# S02-BEAGLEBONE.net
KiCad netlist of a schematic drawn in Altium Designer
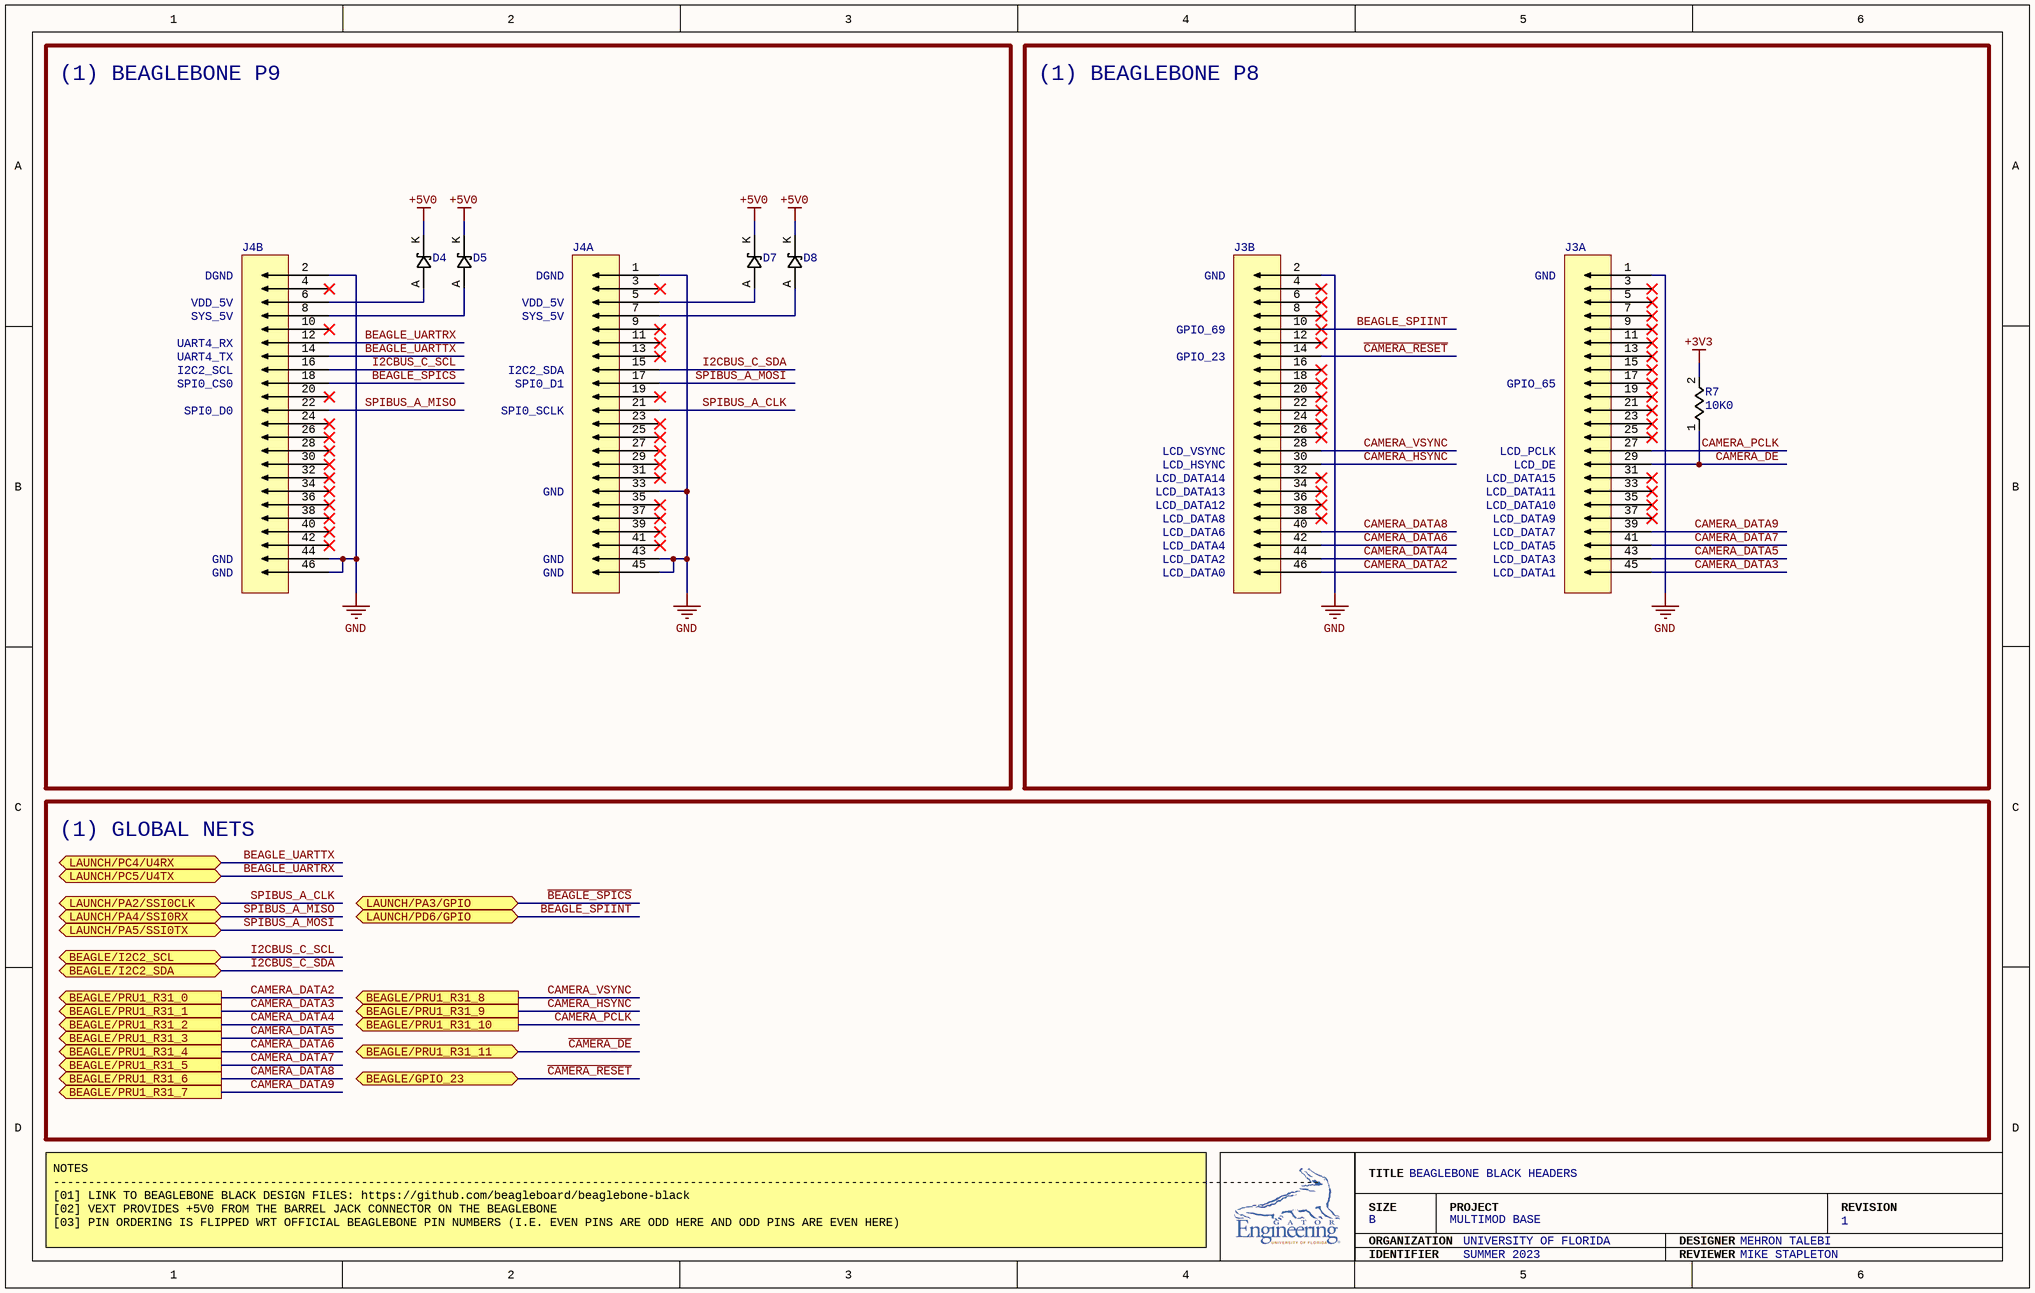
[diagram p0: S02-BEAGLEBONE.SchDoc]

(export (version "E")
  (design (tool "Eeschema 10.0.6"))
  (components
    (comp (ref "D4")
      (value "RBR5L30BDDTE25")
      (footprint "RBR5L30BDDTE25")
      (description "DIODE SCHOTTKY 30V 5A PMDS")
      (libsource (lib "Master") (part "RBR5L30BDDTE25"))
    )
    (comp (ref "D5")
      (value "RBR5L30BDDTE25")
      (footprint "RBR5L30BDDTE25")
      (description "DIODE SCHOTTKY 30V 5A PMDS")
      (libsource (lib "Master") (part "RBR5L30BDDTE25"))
    )
    (comp (ref "D7")
      (value "RBR5L30BDDTE25")
      (footprint "RBR5L30BDDTE25")
      (description "DIODE SCHOTTKY 30V 5A PMDS")
      (libsource (lib "Master") (part "RBR5L30BDDTE25"))
    )
    (comp (ref "D8")
      (value "RBR5L30BDDTE25")
      (footprint "RBR5L30BDDTE25")
      (description "DIODE SCHOTTKY 30V 5A PMDS")
      (libsource (lib "Master") (part "RBR5L30BDDTE25"))
    )
    (comp (ref "J3")
      (value "95278-101-46LF")
      (footprint "95278-101-46LF")
      (description "CONN HEADER SMD 46POS 2.54MM")
      (libsource (lib "Master") (part "95278-101-46LF"))
    )
    (comp (ref "J4")
      (value "95278-101-46LF")
      (footprint "95278-101-46LF")
      (description "CONN HEADER SMD 46POS 2.54MM")
      (libsource (lib "Master") (part "95278-101-46LF"))
    )
    (comp (ref "R7")
      (value "10K0")
      (footprint "RC0805FR-0710KL")
      (description "RES 10K OHM 1% 1/8W 0805")
      (fields (field (name "TOLERANCE") "±1%"))
      (libsource (lib "Master") (part "RC0805FR-0710KL"))
    )
  )
  (nets
    (net (code "1") (name "+3V3") (class "Default")
      (node (ref "R7") (pin "2") (pinfunction "2_2") (pintype "passive"))
    )
    (net (code "2") (name "+5V0") (class "Default")
      (node (ref "D4") (pin "K") (pinfunction "+_K") (pintype "passive"))
      (node (ref "D5") (pin "K") (pinfunction "+_K") (pintype "passive"))
      (node (ref "D7") (pin "K") (pinfunction "+_K") (pintype "passive"))
      (node (ref "D8") (pin "K") (pinfunction "+_K") (pintype "passive"))
    )
    (net (code "3") (name "/BEAGLE_SPICS") (class "Default")
      (node (ref "J4") (pin "18") (pinfunction "18_18") (pintype "passive"))
    )
    (net (code "4") (name "/BEAGLE_SPIINT") (class "Default")
      (node (ref "J3") (pin "10") (pinfunction "10_10") (pintype "passive"))
    )
    (net (code "5") (name "/BEAGLE_UARTRX") (class "Default")
      (node (ref "J4") (pin "12") (pinfunction "12_12") (pintype "passive"))
    )
    (net (code "6") (name "/BEAGLE_UARTTX") (class "Default")
      (node (ref "J4") (pin "14") (pinfunction "14_14") (pintype "passive"))
    )
    (net (code "7") (name "/CAMERA_DATA2") (class "Default")
      (node (ref "J3") (pin "46") (pinfunction "46_46") (pintype "passive"))
    )
    (net (code "8") (name "/CAMERA_DATA3") (class "Default")
      (node (ref "J3") (pin "45") (pinfunction "45_45") (pintype "passive"))
    )
    (net (code "9") (name "/CAMERA_DATA4") (class "Default")
      (node (ref "J3") (pin "44") (pinfunction "44_44") (pintype "passive"))
    )
    (net (code "10") (name "/CAMERA_DATA5") (class "Default")
      (node (ref "J3") (pin "43") (pinfunction "43_43") (pintype "passive"))
    )
    (net (code "11") (name "/CAMERA_DATA6") (class "Default")
      (node (ref "J3") (pin "42") (pinfunction "42_42") (pintype "passive"))
    )
    (net (code "12") (name "/CAMERA_DATA7") (class "Default")
      (node (ref "J3") (pin "41") (pinfunction "41_41") (pintype "passive"))
    )
    (net (code "13") (name "/CAMERA_DATA8") (class "Default")
      (node (ref "J3") (pin "40") (pinfunction "40_40") (pintype "passive"))
    )
    (net (code "14") (name "/CAMERA_DATA9") (class "Default")
      (node (ref "J3") (pin "39") (pinfunction "39_39") (pintype "passive"))
    )
    (net (code "15") (name "/CAMERA_DE") (class "Default")
      (node (ref "J3") (pin "29") (pinfunction "29_29") (pintype "passive"))
      (node (ref "R7") (pin "1") (pinfunction "1_1") (pintype "passive"))
    )
    (net (code "16") (name "/CAMERA_HSYNC") (class "Default")
      (node (ref "J3") (pin "30") (pinfunction "30_30") (pintype "passive"))
    )
    (net (code "17") (name "/CAMERA_PCLK") (class "Default")
      (node (ref "J3") (pin "27") (pinfunction "27_27") (pintype "passive"))
    )
    (net (code "18") (name "/CAMERA_RESET") (class "Default")
      (node (ref "J3") (pin "14") (pinfunction "14_14") (pintype "passive"))
    )
    (net (code "19") (name "/CAMERA_VSYNC") (class "Default")
      (node (ref "J3") (pin "28") (pinfunction "28_28") (pintype "passive"))
    )
    (net (code "20") (name "/I2CBUS_C_SCL") (class "Default")
      (node (ref "J4") (pin "16") (pinfunction "16_16") (pintype "passive"))
    )
    (net (code "21") (name "/I2CBUS_C_SDA") (class "Default")
      (node (ref "J4") (pin "15") (pinfunction "15_15") (pintype "passive"))
    )
    (net (code "22") (name "/SPIBUS_A_CLK") (class "Default")
      (node (ref "J4") (pin "21") (pinfunction "21_21") (pintype "passive"))
    )
    (net (code "23") (name "/SPIBUS_A_MISO") (class "Default")
      (node (ref "J4") (pin "22") (pinfunction "22_22") (pintype "passive"))
    )
    (net (code "24") (name "/SPIBUS_A_MOSI") (class "Default")
      (node (ref "J4") (pin "17") (pinfunction "17_17") (pintype "passive"))
    )
    (net (code "25") (name "GND") (class "Default")
      (node (ref "J3") (pin "1") (pinfunction "1_1") (pintype "passive"))
      (node (ref "J3") (pin "2") (pinfunction "2_2") (pintype "passive"))
      (node (ref "J4") (pin "1") (pinfunction "1_1") (pintype "passive"))
      (node (ref "J4") (pin "2") (pinfunction "2_2") (pintype "passive"))
      (node (ref "J4") (pin "33") (pinfunction "33_33") (pintype "passive"))
      (node (ref "J4") (pin "43") (pinfunction "43_43") (pintype "passive"))
      (node (ref "J4") (pin "44") (pinfunction "44_44") (pintype "passive"))
      (node (ref "J4") (pin "45") (pinfunction "45_45") (pintype "passive"))
      (node (ref "J4") (pin "46") (pinfunction "46_46") (pintype "passive"))
    )
    (net (code "26") (name "Net-(D4--)") (class "Default")
      (node (ref "D4") (pin "A") (pinfunction "-_A") (pintype "passive"))
      (node (ref "J4") (pin "6") (pinfunction "6_6") (pintype "passive"))
    )
    (net (code "27") (name "Net-(D5--)") (class "Default")
      (node (ref "D5") (pin "A") (pinfunction "-_A") (pintype "passive"))
      (node (ref "J4") (pin "8") (pinfunction "8_8") (pintype "passive"))
    )
    (net (code "28") (name "Net-(D7--)") (class "Default")
      (node (ref "D7") (pin "A") (pinfunction "-_A") (pintype "passive"))
      (node (ref "J4") (pin "5") (pinfunction "5_5") (pintype "passive"))
    )
    (net (code "29") (name "Net-(D8--)") (class "Default")
      (node (ref "D8") (pin "A") (pinfunction "-_A") (pintype "passive"))
      (node (ref "J4") (pin "7") (pinfunction "7_7") (pintype "passive"))
    )
    (net (code "30") (name "unconnected-(J3-Pad3)") (class "Default")
      (node (ref "J3") (pin "3") (pinfunction "3_3") (pintype "passive+no_connect"))
    )
    (net (code "31") (name "unconnected-(J3-Pad4)") (class "Default")
      (node (ref "J3") (pin "4") (pinfunction "4_4") (pintype "passive+no_connect"))
    )
    (net (code "32") (name "unconnected-(J3-Pad5)") (class "Default")
      (node (ref "J3") (pin "5") (pinfunction "5_5") (pintype "passive+no_connect"))
    )
    (net (code "33") (name "unconnected-(J3-Pad6)") (class "Default")
      (node (ref "J3") (pin "6") (pinfunction "6_6") (pintype "passive+no_connect"))
    )
    (net (code "34") (name "unconnected-(J3-Pad7)") (class "Default")
      (node (ref "J3") (pin "7") (pinfunction "7_7") (pintype "passive+no_connect"))
    )
    (net (code "35") (name "unconnected-(J3-Pad8)") (class "Default")
      (node (ref "J3") (pin "8") (pinfunction "8_8") (pintype "passive+no_connect"))
    )
    (net (code "36") (name "unconnected-(J3-Pad9)") (class "Default")
      (node (ref "J3") (pin "9") (pinfunction "9_9") (pintype "passive+no_connect"))
    )
    (net (code "37") (name "unconnected-(J3-Pad11)") (class "Default")
      (node (ref "J3") (pin "11") (pinfunction "11_11") (pintype "passive+no_connect"))
    )
    (net (code "38") (name "unconnected-(J3-Pad12)") (class "Default")
      (node (ref "J3") (pin "12") (pinfunction "12_12") (pintype "passive+no_connect"))
    )
    (net (code "39") (name "unconnected-(J3-Pad13)") (class "Default")
      (node (ref "J3") (pin "13") (pinfunction "13_13") (pintype "passive+no_connect"))
    )
    (net (code "40") (name "unconnected-(J3-Pad15)") (class "Default")
      (node (ref "J3") (pin "15") (pinfunction "15_15") (pintype "passive+no_connect"))
    )
    (net (code "41") (name "unconnected-(J3-Pad16)") (class "Default")
      (node (ref "J3") (pin "16") (pinfunction "16_16") (pintype "passive+no_connect"))
    )
    (net (code "42") (name "unconnected-(J3-Pad17)") (class "Default")
      (node (ref "J3") (pin "17") (pinfunction "17_17") (pintype "passive+no_connect"))
    )
    (net (code "43") (name "unconnected-(J3-Pad18)") (class "Default")
      (node (ref "J3") (pin "18") (pinfunction "18_18") (pintype "passive+no_connect"))
    )
    (net (code "44") (name "unconnected-(J3-Pad19)") (class "Default")
      (node (ref "J3") (pin "19") (pinfunction "19_19") (pintype "passive+no_connect"))
    )
    (net (code "45") (name "unconnected-(J3-Pad20)") (class "Default")
      (node (ref "J3") (pin "20") (pinfunction "20_20") (pintype "passive+no_connect"))
    )
    (net (code "46") (name "unconnected-(J3-Pad21)") (class "Default")
      (node (ref "J3") (pin "21") (pinfunction "21_21") (pintype "passive+no_connect"))
    )
    (net (code "47") (name "unconnected-(J3-Pad22)") (class "Default")
      (node (ref "J3") (pin "22") (pinfunction "22_22") (pintype "passive+no_connect"))
    )
    (net (code "48") (name "unconnected-(J3-Pad23)") (class "Default")
      (node (ref "J3") (pin "23") (pinfunction "23_23") (pintype "passive+no_connect"))
    )
    (net (code "49") (name "unconnected-(J3-Pad24)") (class "Default")
      (node (ref "J3") (pin "24") (pinfunction "24_24") (pintype "passive+no_connect"))
    )
    (net (code "50") (name "unconnected-(J3-Pad25)") (class "Default")
      (node (ref "J3") (pin "25") (pinfunction "25_25") (pintype "passive+no_connect"))
    )
    (net (code "51") (name "unconnected-(J3-Pad26)") (class "Default")
      (node (ref "J3") (pin "26") (pinfunction "26_26") (pintype "passive+no_connect"))
    )
    (net (code "52") (name "unconnected-(J3-Pad31)") (class "Default")
      (node (ref "J3") (pin "31") (pinfunction "31_31") (pintype "passive+no_connect"))
    )
    (net (code "53") (name "unconnected-(J3-Pad32)") (class "Default")
      (node (ref "J3") (pin "32") (pinfunction "32_32") (pintype "passive+no_connect"))
    )
    (net (code "54") (name "unconnected-(J3-Pad33)") (class "Default")
      (node (ref "J3") (pin "33") (pinfunction "33_33") (pintype "passive+no_connect"))
    )
    (net (code "55") (name "unconnected-(J3-Pad34)") (class "Default")
      (node (ref "J3") (pin "34") (pinfunction "34_34") (pintype "passive+no_connect"))
    )
    (net (code "56") (name "unconnected-(J3-Pad35)") (class "Default")
      (node (ref "J3") (pin "35") (pinfunction "35_35") (pintype "passive+no_connect"))
    )
    (net (code "57") (name "unconnected-(J3-Pad36)") (class "Default")
      (node (ref "J3") (pin "36") (pinfunction "36_36") (pintype "passive+no_connect"))
    )
    (net (code "58") (name "unconnected-(J3-Pad37)") (class "Default")
      (node (ref "J3") (pin "37") (pinfunction "37_37") (pintype "passive+no_connect"))
    )
    (net (code "59") (name "unconnected-(J3-Pad38)") (class "Default")
      (node (ref "J3") (pin "38") (pinfunction "38_38") (pintype "passive+no_connect"))
    )
    (net (code "60") (name "unconnected-(J4-Pad3)") (class "Default")
      (node (ref "J4") (pin "3") (pinfunction "3_3") (pintype "passive+no_connect"))
    )
    (net (code "61") (name "unconnected-(J4-Pad4)") (class "Default")
      (node (ref "J4") (pin "4") (pinfunction "4_4") (pintype "passive+no_connect"))
    )
    (net (code "62") (name "unconnected-(J4-Pad9)") (class "Default")
      (node (ref "J4") (pin "9") (pinfunction "9_9") (pintype "passive+no_connect"))
    )
    (net (code "63") (name "unconnected-(J4-Pad10)") (class "Default")
      (node (ref "J4") (pin "10") (pinfunction "10_10") (pintype "passive+no_connect"))
    )
    (net (code "64") (name "unconnected-(J4-Pad11)") (class "Default")
      (node (ref "J4") (pin "11") (pinfunction "11_11") (pintype "passive+no_connect"))
    )
    (net (code "65") (name "unconnected-(J4-Pad13)") (class "Default")
      (node (ref "J4") (pin "13") (pinfunction "13_13") (pintype "passive+no_connect"))
    )
    (net (code "66") (name "unconnected-(J4-Pad19)") (class "Default")
      (node (ref "J4") (pin "19") (pinfunction "19_19") (pintype "passive+no_connect"))
    )
    (net (code "67") (name "unconnected-(J4-Pad20)") (class "Default")
      (node (ref "J4") (pin "20") (pinfunction "20_20") (pintype "passive+no_connect"))
    )
    (net (code "68") (name "unconnected-(J4-Pad23)") (class "Default")
      (node (ref "J4") (pin "23") (pinfunction "23_23") (pintype "passive+no_connect"))
    )
    (net (code "69") (name "unconnected-(J4-Pad24)") (class "Default")
      (node (ref "J4") (pin "24") (pinfunction "24_24") (pintype "passive+no_connect"))
    )
    (net (code "70") (name "unconnected-(J4-Pad25)") (class "Default")
      (node (ref "J4") (pin "25") (pinfunction "25_25") (pintype "passive+no_connect"))
    )
    (net (code "71") (name "unconnected-(J4-Pad26)") (class "Default")
      (node (ref "J4") (pin "26") (pinfunction "26_26") (pintype "passive+no_connect"))
    )
    (net (code "72") (name "unconnected-(J4-Pad27)") (class "Default")
      (node (ref "J4") (pin "27") (pinfunction "27_27") (pintype "passive+no_connect"))
    )
    (net (code "73") (name "unconnected-(J4-Pad28)") (class "Default")
      (node (ref "J4") (pin "28") (pinfunction "28_28") (pintype "passive+no_connect"))
    )
    (net (code "74") (name "unconnected-(J4-Pad29)") (class "Default")
      (node (ref "J4") (pin "29") (pinfunction "29_29") (pintype "passive+no_connect"))
    )
    (net (code "75") (name "unconnected-(J4-Pad30)") (class "Default")
      (node (ref "J4") (pin "30") (pinfunction "30_30") (pintype "passive+no_connect"))
    )
    (net (code "76") (name "unconnected-(J4-Pad31)") (class "Default")
      (node (ref "J4") (pin "31") (pinfunction "31_31") (pintype "passive+no_connect"))
    )
    (net (code "77") (name "unconnected-(J4-Pad32)") (class "Default")
      (node (ref "J4") (pin "32") (pinfunction "32_32") (pintype "passive+no_connect"))
    )
    (net (code "78") (name "unconnected-(J4-Pad34)") (class "Default")
      (node (ref "J4") (pin "34") (pinfunction "34_34") (pintype "passive+no_connect"))
    )
    (net (code "79") (name "unconnected-(J4-Pad35)") (class "Default")
      (node (ref "J4") (pin "35") (pinfunction "35_35") (pintype "passive+no_connect"))
    )
    (net (code "80") (name "unconnected-(J4-Pad36)") (class "Default")
      (node (ref "J4") (pin "36") (pinfunction "36_36") (pintype "passive+no_connect"))
    )
    (net (code "81") (name "unconnected-(J4-Pad37)") (class "Default")
      (node (ref "J4") (pin "37") (pinfunction "37_37") (pintype "passive+no_connect"))
    )
    (net (code "82") (name "unconnected-(J4-Pad38)") (class "Default")
      (node (ref "J4") (pin "38") (pinfunction "38_38") (pintype "passive+no_connect"))
    )
    (net (code "83") (name "unconnected-(J4-Pad39)") (class "Default")
      (node (ref "J4") (pin "39") (pinfunction "39_39") (pintype "passive+no_connect"))
    )
    (net (code "84") (name "unconnected-(J4-Pad40)") (class "Default")
      (node (ref "J4") (pin "40") (pinfunction "40_40") (pintype "passive+no_connect"))
    )
    (net (code "85") (name "unconnected-(J4-Pad41)") (class "Default")
      (node (ref "J4") (pin "41") (pinfunction "41_41") (pintype "passive+no_connect"))
    )
    (net (code "86") (name "unconnected-(J4-Pad42)") (class "Default")
      (node (ref "J4") (pin "42") (pinfunction "42_42") (pintype "passive+no_connect"))
    )
  )
)
